# 20_AI_Board.net
KiCad netlist of a schematic drawn in Altium Designer
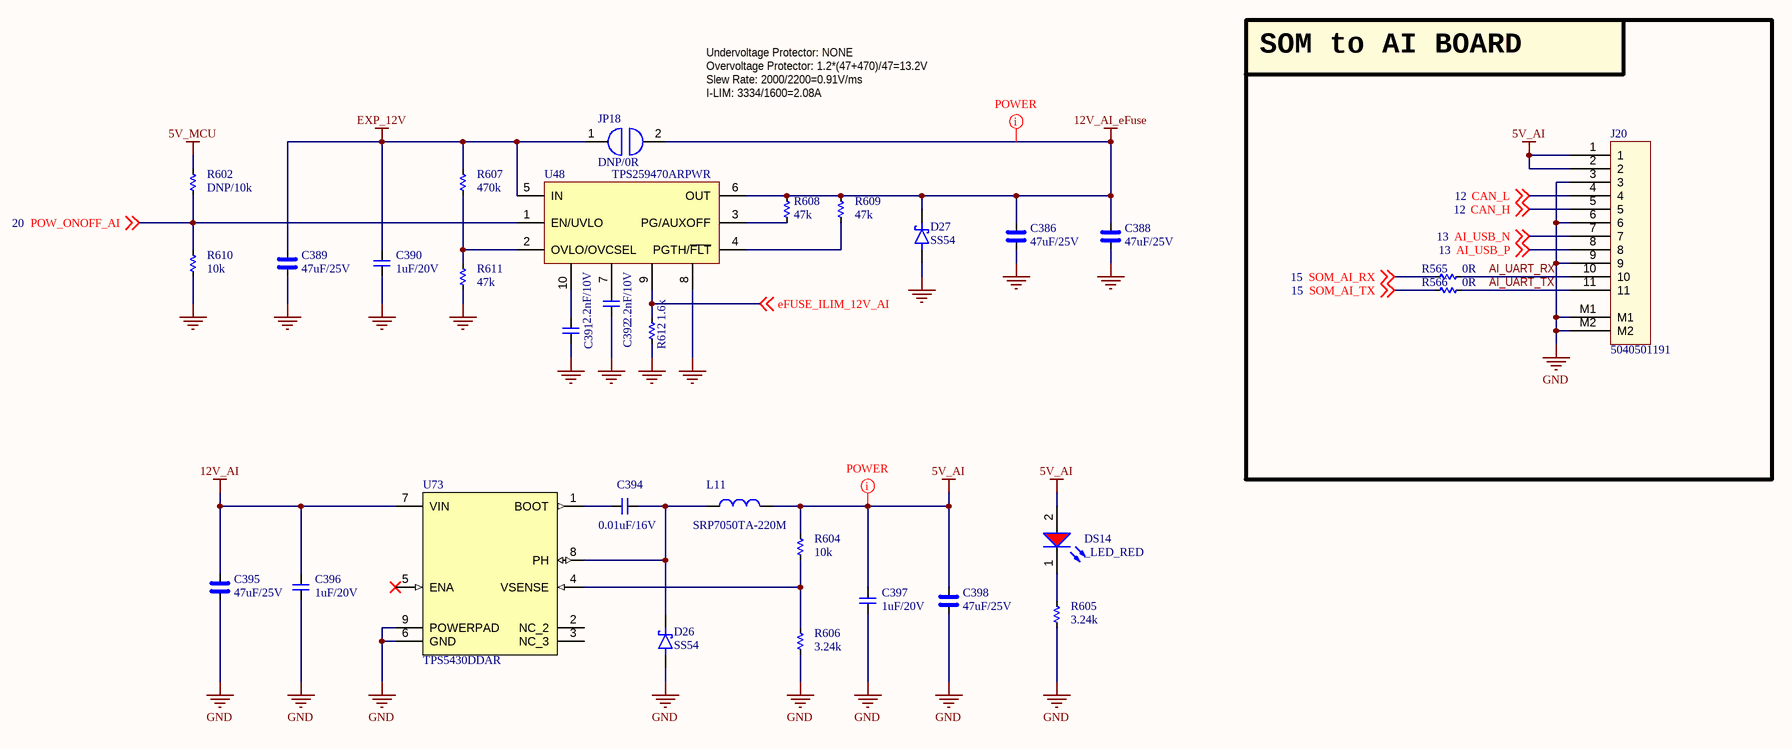
[diagram p0: 20_AI_Board.SchDoc]

(export (version "E")
  (design (tool "Eeschema 10.0.6"))
  (components
    (comp (ref "C386")
      (value "47uF/25V")
      (footprint "CAP_C_3225X80")
      (description "CAP High Value")
      (libsource (lib "LABLIB") (part "_CAP_C_High_2"))
    )
    (comp (ref "C388")
      (value "47uF/25V")
      (footprint "CAP_C_3225X80")
      (description "CAP High Value")
      (libsource (lib "LABLIB") (part "_CAP_C_High_2"))
    )
    (comp (ref "C389")
      (value "47uF/25V")
      (footprint "CAP_C_3225X80")
      (description "CAP High Value")
      (libsource (lib "LABLIB") (part "_CAP_C_High_2"))
    )
    (comp (ref "C390")
      (value "1uF/20V")
      (footprint "CAP_C_1005X60")
      (description "CAP")
      (libsource (lib "LABLIB") (part "_CAP_C_2"))
    )
    (comp (ref "C391")
      (value "2.2nF/10V")
      (footprint "CAP_C_1005X60")
      (description "CAP")
      (libsource (lib "LABLIB") (part "_CAP_C_2"))
    )
    (comp (ref "C392")
      (value "2.2nF/10V")
      (footprint "CAP_C_1005X60")
      (description "CAP")
      (libsource (lib "LABLIB") (part "_CAP_C_2"))
    )
    (comp (ref "C394")
      (value "0.01uF/16V")
      (footprint "CAP_C_1608X80")
      (description "CAP")
      (libsource (lib "LABLIB") (part "_CAP_C_2"))
    )
    (comp (ref "C395")
      (value "47uF/25V")
      (footprint "CAP_C_3225X80")
      (description "CAP High Value")
      (libsource (lib "LABLIB") (part "_CAP_C_High_2"))
    )
    (comp (ref "C396")
      (value "1uF/20V")
      (footprint "CAP_C_1005X60")
      (description "CAP")
      (libsource (lib "LABLIB") (part "_CAP_C_2"))
    )
    (comp (ref "C397")
      (value "1uF/20V")
      (footprint "CAP_C_1005X60")
      (description "CAP")
      (libsource (lib "LABLIB") (part "_CAP_C_2"))
    )
    (comp (ref "C398")
      (value "47uF/25V")
      (footprint "CAP_C_3225X80")
      (description "CAP High Value")
      (libsource (lib "LABLIB") (part "_CAP_C_High_2"))
    )
    (comp (ref "D26")
      (value "SS54")
      (footprint "DO-214AC_SMA")
      (description "DIODE SCHOTTKY")
      (libsource (lib "LABLIB") (part "DIODE SCHOTTKY"))
    )
    (comp (ref "D27")
      (value "SS54")
      (footprint "DO-214AC_SMA")
      (description "DIODE SCHOTTKY")
      (libsource (lib "LABLIB") (part "DIODE SCHOTTKY"))
    )
    (comp (ref "DS14") (value "_LED_RED") (footprint "LED_0603") (libsource (lib "LABLIB") (part "_LED_RED")))
    (comp (ref "J20")
      (value "5040501191")
      (footprint "MOLEX_5040501191")
      (libsource (lib "LABLIB") (part "Header 11x1_2M"))
    )
    (comp (ref "JP18") (value "DNP/0R") (footprint "JUMPER_1608") (libsource (lib "EXP_V1") (part "JUMPER")))
    (comp (ref "L11")
      (value "SRP7050TA-220M")
      (footprint "PSM6050")
      (description "FIXED IND 22UH 2.5A 170 MOHM SMD")
      (libsource (lib "LABLIB") (part "SRP7050TA-220M"))
    )
    (comp (ref "R565")
      (value "0R")
      (footprint "RES_C_1005X40")
      (description "RES")
      (libsource (lib "LABLIB") (part "_RES_B_2"))
    )
    (comp (ref "R566")
      (value "0R")
      (footprint "RES_C_1005X40")
      (description "RES")
      (libsource (lib "LABLIB") (part "_RES_B_2"))
    )
    (comp (ref "R602")
      (value "DNP/10k")
      (footprint "RES_C_1005X40")
      (description "RES")
      (libsource (lib "LABLIB") (part "_RES_B_2"))
    )
    (comp (ref "R604")
      (value "10k")
      (footprint "RES_C_1005X40")
      (description "RES")
      (libsource (lib "LABLIB") (part "_RES_B_2"))
    )
    (comp (ref "R605")
      (value "3.24k")
      (footprint "RES_C_1005X40")
      (description "RES")
      (libsource (lib "LABLIB") (part "_RES_B_2"))
    )
    (comp (ref "R606")
      (value "3.24k")
      (footprint "RES_C_1005X40")
      (description "RES")
      (libsource (lib "LABLIB") (part "_RES_B_2"))
    )
    (comp (ref "R607")
      (value "470k")
      (footprint "RES_C_1005X40")
      (description "RES")
      (libsource (lib "LABLIB") (part "_RES_B_2"))
    )
    (comp (ref "R608")
      (value "47k")
      (footprint "RES_C_1005X40")
      (description "RES")
      (libsource (lib "LABLIB") (part "_RES_B_2"))
    )
    (comp (ref "R609")
      (value "47k")
      (footprint "RES_C_1005X40")
      (description "RES")
      (libsource (lib "LABLIB") (part "_RES_B_2"))
    )
    (comp (ref "R610")
      (value "10k")
      (footprint "RES_C_1005X40")
      (description "RES")
      (libsource (lib "LABLIB") (part "_RES_B_2"))
    )
    (comp (ref "R611")
      (value "47k")
      (footprint "RES_C_1005X40")
      (description "RES")
      (libsource (lib "LABLIB") (part "_RES_B_2"))
    )
    (comp (ref "R612")
      (value "1.6k")
      (footprint "RES_C_1005X40")
      (description "RES")
      (libsource (lib "LABLIB") (part "_RES_B_2"))
    )
    (comp (ref "U48")
      (value "TPS259470ARPWR")
      (footprint "VQFN-HR-10")
      (libsource (lib "EXP_HW_V3") (part "TPS259470ARPWR"))
    )
    (comp (ref "U73")
      (value "TPS5430DDAR")
      (footprint "TPS54531DDAR")
      (description "IC REG BUCK ADJ 3A 8SOPWR")
      (libsource (lib "EXP_HW_V3") (part "TPS5430DDAR"))
    )
  )
  (nets
    (net (code "1") (name "/AI_UART_RX") (class "Default")
      (node (ref "J20") (pin "10") (pinfunction "10_10") (pintype "passive"))
      (node (ref "R565") (pin "2") (pinfunction "2_2") (pintype "passive"))
    )
    (net (code "2") (name "/AI_UART_TX") (class "Default")
      (node (ref "J20") (pin "11") (pinfunction "11_11") (pintype "passive"))
      (node (ref "R566") (pin "2") (pinfunction "2_2") (pintype "passive"))
    )
    (net (code "3") (name "5V_AI") (class "Default")
      (node (ref "C397") (pin "2") (pinfunction "2_2") (pintype "passive"))
      (node (ref "C398") (pin "2") (pinfunction "2_2") (pintype "passive"))
      (node (ref "DS14") (pin "2") (pinfunction "A_2") (pintype "passive"))
      (node (ref "J20") (pin "1") (pinfunction "1_1") (pintype "passive"))
      (node (ref "J20") (pin "2") (pinfunction "2_2") (pintype "passive"))
      (node (ref "L11") (pin "2") (pinfunction "2_2") (pintype "passive"))
      (node (ref "R604") (pin "2") (pinfunction "2_2") (pintype "passive"))
    )
    (net (code "4") (name "5V_MCU") (class "Default")
      (node (ref "R602") (pin "1") (pinfunction "1_1") (pintype "passive"))
    )
    (net (code "5") (name "12V_AI") (class "Default")
      (node (ref "C395") (pin "2") (pinfunction "2_2") (pintype "passive"))
      (node (ref "C396") (pin "2") (pinfunction "2_2") (pintype "passive"))
      (node (ref "U73") (pin "7") (pinfunction "VIN_7") (pintype "power_in"))
    )
    (net (code "6") (name "12V_AI_eFuse") (class "Default")
      (node (ref "C386") (pin "2") (pinfunction "2_2") (pintype "passive"))
      (node (ref "C388") (pin "2") (pinfunction "2_2") (pintype "passive"))
      (node (ref "D27") (pin "1") (pinfunction "K_1") (pintype "passive"))
      (node (ref "JP18") (pin "2") (pinfunction "2_2") (pintype "passive"))
      (node (ref "R608") (pin "2") (pinfunction "2_2") (pintype "passive"))
      (node (ref "R609") (pin "2") (pinfunction "2_2") (pintype "passive"))
      (node (ref "U48") (pin "6") (pinfunction "OUT_6") (pintype "passive"))
    )
    (net (code "7") (name "AI_USB_N") (class "Default")
      (node (ref "J20") (pin "7") (pinfunction "7_7") (pintype "passive"))
    )
    (net (code "8") (name "AI_USB_P") (class "Default")
      (node (ref "J20") (pin "8") (pinfunction "8_8") (pintype "passive"))
    )
    (net (code "9") (name "CAN_H") (class "Default")
      (node (ref "J20") (pin "5") (pinfunction "5_5") (pintype "passive"))
    )
    (net (code "10") (name "CAN_L") (class "Default")
      (node (ref "J20") (pin "4") (pinfunction "4_4") (pintype "passive"))
    )
    (net (code "11") (name "EXP_12V") (class "Default")
      (node (ref "C389") (pin "2") (pinfunction "2_2") (pintype "passive"))
      (node (ref "C390") (pin "2") (pinfunction "2_2") (pintype "passive"))
      (node (ref "JP18") (pin "1") (pinfunction "1_1") (pintype "passive"))
      (node (ref "R607") (pin "2") (pinfunction "2_2") (pintype "passive"))
      (node (ref "U48") (pin "5") (pinfunction "IN_5") (pintype "passive"))
    )
    (net (code "12") (name "GND") (class "Default")
      (node (ref "C386") (pin "1") (pinfunction "1_1") (pintype "passive"))
      (node (ref "C388") (pin "1") (pinfunction "1_1") (pintype "passive"))
      (node (ref "C389") (pin "1") (pinfunction "1_1") (pintype "passive"))
      (node (ref "C390") (pin "1") (pinfunction "1_1") (pintype "passive"))
      (node (ref "C391") (pin "1") (pinfunction "1_1") (pintype "passive"))
      (node (ref "C392") (pin "1") (pinfunction "1_1") (pintype "passive"))
      (node (ref "C395") (pin "1") (pinfunction "1_1") (pintype "passive"))
      (node (ref "C396") (pin "1") (pinfunction "1_1") (pintype "passive"))
      (node (ref "C397") (pin "1") (pinfunction "1_1") (pintype "passive"))
      (node (ref "C398") (pin "1") (pinfunction "1_1") (pintype "passive"))
      (node (ref "D26") (pin "2") (pinfunction "A_2") (pintype "passive"))
      (node (ref "D27") (pin "2") (pinfunction "A_2") (pintype "passive"))
      (node (ref "J20") (pin "3") (pinfunction "3_3") (pintype "passive"))
      (node (ref "J20") (pin "6") (pinfunction "6_6") (pintype "passive"))
      (node (ref "J20") (pin "9") (pinfunction "9_9") (pintype "passive"))
      (node (ref "J20") (pin "M1") (pinfunction "M1_M1") (pintype "passive"))
      (node (ref "J20") (pin "M2") (pinfunction "M2_M2") (pintype "passive"))
      (node (ref "R605") (pin "1") (pinfunction "1_1") (pintype "passive"))
      (node (ref "R606") (pin "1") (pinfunction "1_1") (pintype "passive"))
      (node (ref "R610") (pin "2") (pinfunction "2_2") (pintype "passive"))
      (node (ref "R611") (pin "1") (pinfunction "1_1") (pintype "passive"))
      (node (ref "R612") (pin "1") (pinfunction "1_1") (pintype "passive"))
      (node (ref "U48") (pin "8") (pinfunction "8_8") (pintype "passive"))
      (node (ref "U73") (pin "6") (pinfunction "GND_6") (pintype "power_in"))
      (node (ref "U73") (pin "9") (pinfunction "POWERPAD_9") (pintype "power_in"))
    )
    (net (code "13") (name "Net-(C391-Pad2)") (class "Default")
      (node (ref "C391") (pin "2") (pinfunction "2_2") (pintype "passive"))
      (node (ref "U48") (pin "10") (pinfunction "10_10") (pintype "passive"))
    )
    (net (code "14") (name "Net-(C392-Pad2)") (class "Default")
      (node (ref "C392") (pin "2") (pinfunction "2_2") (pintype "passive"))
      (node (ref "U48") (pin "7") (pinfunction "7_7") (pintype "passive"))
    )
    (net (code "15") (name "Net-(D26-K)") (class "Default")
      (node (ref "C394") (pin "1") (pinfunction "1_1") (pintype "passive"))
      (node (ref "D26") (pin "1") (pinfunction "K_1") (pintype "passive"))
      (node (ref "L11") (pin "1") (pinfunction "1_1") (pintype "passive"))
      (node (ref "U73") (pin "8") (pinfunction "PH_8") (pintype "bidirectional"))
    )
    (net (code "16") (name "Net-(DS14-K)") (class "Default")
      (node (ref "DS14") (pin "1") (pinfunction "K_1") (pintype "passive"))
      (node (ref "R605") (pin "2") (pinfunction "2_2") (pintype "passive"))
    )
    (net (code "17") (name "Net-(U48-OVLO{slash}OVCSEL)") (class "Default")
      (node (ref "R607") (pin "1") (pinfunction "1_1") (pintype "passive"))
      (node (ref "R611") (pin "2") (pinfunction "2_2") (pintype "passive"))
      (node (ref "U48") (pin "2") (pinfunction "OVLO/OVCSEL_2") (pintype "passive"))
    )
    (net (code "18") (name "Net-(U48-PGTH{slash}~{FLT})") (class "Default")
      (node (ref "R609") (pin "1") (pinfunction "1_1") (pintype "passive"))
      (node (ref "U48") (pin "4") (pinfunction "PGTH/~{FLT}_4") (pintype "passive"))
    )
    (net (code "19") (name "Net-(U48-PG{slash}AUXOFF)") (class "Default")
      (node (ref "R608") (pin "1") (pinfunction "1_1") (pintype "passive"))
      (node (ref "U48") (pin "3") (pinfunction "PG/AUXOFF_3") (pintype "passive"))
    )
    (net (code "20") (name "Net-(U73-BOOT)") (class "Default")
      (node (ref "C394") (pin "2") (pinfunction "2_2") (pintype "passive"))
      (node (ref "U73") (pin "1") (pinfunction "BOOT_1") (pintype "output"))
    )
    (net (code "21") (name "Net-(U73-VSENSE)") (class "Default")
      (node (ref "R604") (pin "1") (pinfunction "1_1") (pintype "passive"))
      (node (ref "R606") (pin "2") (pinfunction "2_2") (pintype "passive"))
      (node (ref "U73") (pin "4") (pinfunction "VSENSE_4") (pintype "input"))
    )
    (net (code "22") (name "POW_ONOFF_AI") (class "Default")
      (node (ref "R602") (pin "2") (pinfunction "2_2") (pintype "passive"))
      (node (ref "R610") (pin "1") (pinfunction "1_1") (pintype "passive"))
      (node (ref "U48") (pin "1") (pinfunction "EN/UVLO_1") (pintype "passive"))
    )
    (net (code "23") (name "SOM_AI_RX") (class "Default")
      (node (ref "R565") (pin "1") (pinfunction "1_1") (pintype "passive"))
    )
    (net (code "24") (name "SOM_AI_TX") (class "Default")
      (node (ref "R566") (pin "1") (pinfunction "1_1") (pintype "passive"))
    )
    (net (code "25") (name "eFUSE_ILIM_12V_AI") (class "Default")
      (node (ref "R612") (pin "2") (pinfunction "2_2") (pintype "passive"))
      (node (ref "U48") (pin "9") (pinfunction "9_9") (pintype "passive"))
    )
    (net (code "26") (name "unconnected-(U73-ENA-Pad5)") (class "Default")
      (node (ref "U73") (pin "5") (pinfunction "ENA_5") (pintype "input+no_connect"))
    )
    (net (code "27") (name "unconnected-(U73-NC_2-Pad2)") (class "Default")
      (node (ref "U73") (pin "2") (pinfunction "NC_2_2") (pintype "passive"))
    )
    (net (code "28") (name "unconnected-(U73-NC_3-Pad3)") (class "Default")
      (node (ref "U73") (pin "3") (pinfunction "NC_3_3") (pintype "passive"))
    )
  )
)
